# Sheet3.net
KiCad netlist of a schematic drawn in Altium Designer
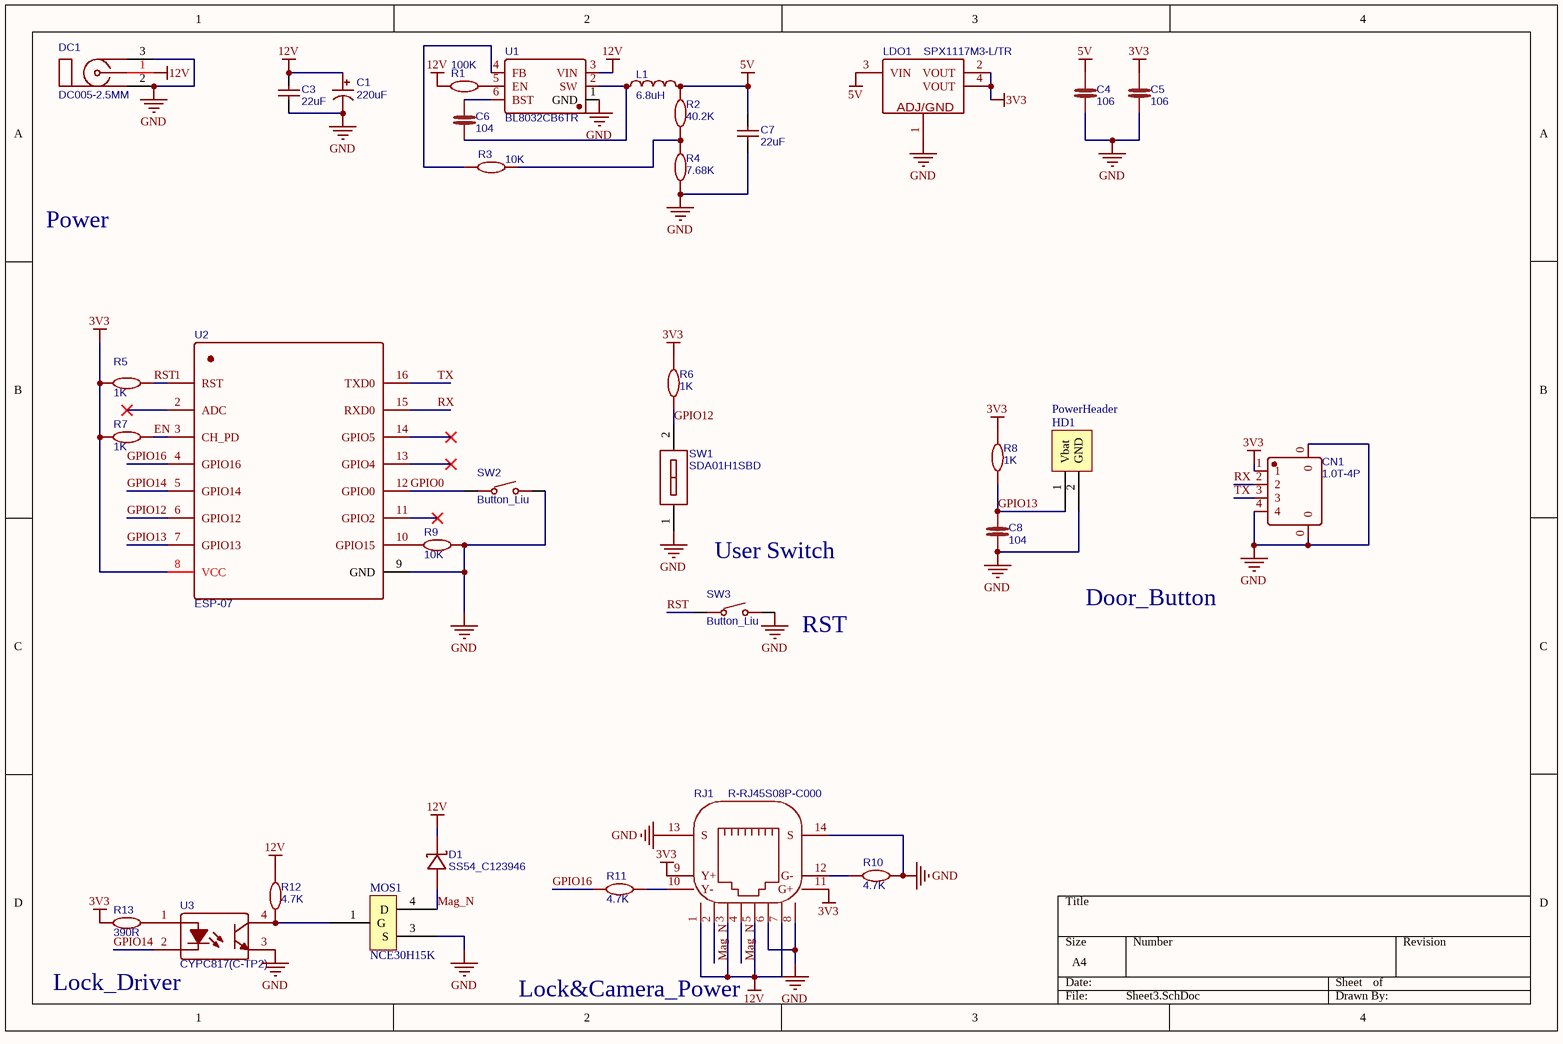
[diagram p0: Sheet3.SchDoc]

(export (version "E")
  (design (tool "Eeschema 10.0.6"))
  (components
    (comp (ref "C1")
      (value "220uF")
      (footprint "CAP-SMD_BD10.0-L10.3-W10.3-FD")
      (fields
        (field (name "BOM_MANUFACTURER PART") "RVT1H221M1010")
        (field (name "BOM_SUPPLIER PART") "C3358")
      )
      (libsource (lib "Power_saving") (part "220uF"))
    )
    (comp (ref "C3")
      (value "22uF")
      (footprint "0805")
      (fields
        (field (name "BOM_MANUFACTURER PART") "TMK212BJ105KG-T")
        (field (name "BOM_SUPPLIER PART") "C92829")
      )
      (libsource (lib "2019_Nudec") (part "1uF"))
    )
    (comp (ref "C4")
      (value "106")
      (footprint "0805")
      (fields (field (name "BOM_MANUFACTURER PART") "?") (field (name "CONTRIBUTOR") "SparkFun"))
      (libsource (lib "抄封装") (part "0.1UF-16V(+-10%)(0402)"))
    )
    (comp (ref "C5")
      (value "106")
      (footprint "0805")
      (fields (field (name "BOM_MANUFACTURER PART") "?") (field (name "CONTRIBUTOR") "SparkFun"))
      (libsource (lib "抄封装") (part "0.1UF-16V(+-10%)(0402)"))
    )
    (comp (ref "C6")
      (value "104")
      (footprint "0402")
      (fields (field (name "BOM_MANUFACTURER PART") "?") (field (name "CONTRIBUTOR") "SparkFun"))
      (libsource (lib "抄封装") (part "0.1UF-16V(+-10%)(0402)"))
    )
    (comp (ref "C7")
      (value "22uF")
      (footprint "0805")
      (fields
        (field (name "BOM_MANUFACTURER PART") "TMK212BJ105KG-T")
        (field (name "BOM_SUPPLIER PART") "C92829")
      )
      (libsource (lib "2019_Nudec") (part "1uF"))
    )
    (comp (ref "C8")
      (value "104")
      (footprint "0402")
      (fields (field (name "BOM_MANUFACTURER PART") "?") (field (name "CONTRIBUTOR") "SparkFun"))
      (libsource (lib "抄封装") (part "0.1UF-16V(+-10%)(0402)"))
    )
    (comp (ref "CN1")
      (value "1.0T-4P")
      (footprint "1.0T-4P-LT")
      (fields (field (name "BOM_SUPPLIER PART") "C145961") (field (name "CONTRIBUTOR") "LCSC"))
      (libsource (lib "Power_saving") (part "1.0T-4P"))
    )
    (comp (ref "D1")
      (value "SS54_C123946")
      (footprint "SMA_L4.4-W2.8-LS5.4-RD")
      (fields
        (field (name "BOM_SUPPLIER PART") "C123946")
        (field (name "BOM_MANUFACTURER PART") "SS54")
        (field (name "CONTRIBUTOR") "LCSC")
      )
      (libsource (lib "Arduino_4G_Weather_Station") (part "SS54_C123946"))
    )
    (comp (ref "DC1")
      (value "DC005-2.5MM")
      (footprint "DC-5020")
      (fields (field (name "BOM_SUPPLIER PART") "C111573"))
      (libsource (lib "Dr.Deng") (part "DC005-2.5MM"))
    )
    (comp (ref "HD1")
      (value "PowerHeader")
      (footprint "PowerHeader")
      (libsource (lib "eg2104") (part "PowerHeader"))
    )
    (comp (ref "L1")
      (value "6.8uH")
      (footprint "L-SMD-6.0X6.0X4.7")
      (fields
        (field (name "BOM_SUPPLIER PART") "C354631")
        (field (name "BOM_MANUFACTURER PART") "CKCS6045-6.8uH/M")
        (field (name "CONTRIBUTOR") "LCSC")
      )
      (libsource (lib "2019_Nudec") (part "6.8uH"))
    )
    (comp (ref "LDO1")
      (value "SPX1117M3-L/TR")
      (footprint "SOT-223")
      (fields (field (name "BOM_SUPPLIER PART") "C67402"))
      (libsource (lib "Arduino_4G_Weather_Station") (part "SPX1117M3-L/TR"))
    )
    (comp (ref "MOS1")
      (value "NCE30H15K")
      (footprint "DPAK228P970X238-3N")
      (libsource (lib "eg2104") (part "IRLR7843"))
    )
    (comp (ref "R1")
      (value "100K")
      (footprint "0402")
      (fields
        (field (name "BOM_SUPPLIER PART") "C340521")
        (field (name "BOM_MANUFACTURER PART") "RMC1/16S-102JTH-M")
        (field (name "CONTRIBUTOR") "LCSC")
      )
      (libsource (lib "抄封装") (part "1K"))
    )
    (comp (ref "R2")
      (value "40.2K")
      (footprint "0402")
      (fields
        (field (name "BOM_SUPPLIER PART") "C340521")
        (field (name "BOM_MANUFACTURER PART") "RMC1/16S-102JTH-M")
        (field (name "CONTRIBUTOR") "LCSC")
      )
      (libsource (lib "抄封装") (part "1K"))
    )
    (comp (ref "R3")
      (value "10K")
      (footprint "0402")
      (fields
        (field (name "BOM_SUPPLIER PART") "C340521")
        (field (name "BOM_MANUFACTURER PART") "RMC1/16S-102JTH-M")
        (field (name "CONTRIBUTOR") "LCSC")
      )
      (libsource (lib "抄封装") (part "1K"))
    )
    (comp (ref "R4")
      (value "7.68K")
      (footprint "0402")
      (fields
        (field (name "BOM_SUPPLIER PART") "C340521")
        (field (name "BOM_MANUFACTURER PART") "RMC1/16S-102JTH-M")
        (field (name "CONTRIBUTOR") "LCSC")
      )
      (libsource (lib "抄封装") (part "1K"))
    )
    (comp (ref "R5")
      (value "1K")
      (footprint "0402")
      (fields
        (field (name "BOM_SUPPLIER PART") "C340521")
        (field (name "BOM_MANUFACTURER PART") "RMC1/16S-102JTH-M")
        (field (name "CONTRIBUTOR") "LCSC")
      )
      (libsource (lib "抄封装") (part "1K"))
    )
    (comp (ref "R6")
      (value "1K")
      (footprint "0402")
      (fields
        (field (name "BOM_SUPPLIER PART") "C340521")
        (field (name "BOM_MANUFACTURER PART") "RMC1/16S-102JTH-M")
        (field (name "CONTRIBUTOR") "LCSC")
      )
      (libsource (lib "抄封装") (part "1K"))
    )
    (comp (ref "R7")
      (value "1K")
      (footprint "0402")
      (fields
        (field (name "BOM_SUPPLIER PART") "C340521")
        (field (name "BOM_MANUFACTURER PART") "RMC1/16S-102JTH-M")
        (field (name "CONTRIBUTOR") "LCSC")
      )
      (libsource (lib "抄封装") (part "1K"))
    )
    (comp (ref "R8")
      (value "1K")
      (footprint "0402")
      (fields
        (field (name "BOM_SUPPLIER PART") "C340521")
        (field (name "BOM_MANUFACTURER PART") "RMC1/16S-102JTH-M")
        (field (name "CONTRIBUTOR") "LCSC")
      )
      (libsource (lib "抄封装") (part "1K"))
    )
    (comp (ref "R9")
      (value "10K")
      (footprint "0402")
      (fields
        (field (name "BOM_SUPPLIER PART") "C340521")
        (field (name "BOM_MANUFACTURER PART") "RMC1/16S-102JTH-M")
        (field (name "CONTRIBUTOR") "LCSC")
      )
      (libsource (lib "抄封装") (part "1K"))
    )
    (comp (ref "R10")
      (value "4.7K")
      (footprint "0402")
      (fields
        (field (name "BOM_SUPPLIER PART") "C340521")
        (field (name "BOM_MANUFACTURER PART") "RMC1/16S-102JTH-M")
        (field (name "CONTRIBUTOR") "LCSC")
      )
      (libsource (lib "抄封装") (part "1K"))
    )
    (comp (ref "R11")
      (value "4.7K")
      (footprint "0402")
      (fields
        (field (name "BOM_SUPPLIER PART") "C340521")
        (field (name "BOM_MANUFACTURER PART") "RMC1/16S-102JTH-M")
        (field (name "CONTRIBUTOR") "LCSC")
      )
      (libsource (lib "抄封装") (part "1K"))
    )
    (comp (ref "R12")
      (value "4.7K")
      (footprint "0402")
      (fields
        (field (name "BOM_SUPPLIER PART") "C340521")
        (field (name "BOM_MANUFACTURER PART") "RMC1/16S-102JTH-M")
        (field (name "CONTRIBUTOR") "LCSC")
      )
      (libsource (lib "抄封装") (part "1K"))
    )
    (comp (ref "R13")
      (value "390R")
      (footprint "0402")
      (fields
        (field (name "BOM_SUPPLIER PART") "C340521")
        (field (name "BOM_MANUFACTURER PART") "RMC1/16S-102JTH-M")
        (field (name "CONTRIBUTOR") "LCSC")
      )
      (libsource (lib "抄封装") (part "1K"))
    )
    (comp (ref "RJ1")
      (value "R-RJ45S08P-C000")
      (footprint "RJ45-TH_12PIN_R-RJ45S08P-C000_PITCH2.54-TL")
      (fields (field (name "BOM_SUPPLIER PART") "C386764") (field (name "CONTRIBUTOR") "LCSC"))
      (libsource (lib "Arduino_4G_Weather_Station") (part "R-RJ45S08P-C000"))
    )
    (comp (ref "SW1")
      (value "SDA01H1SBD")
      (footprint "SDA01H1SBD")
      (fields (field (name "BOM_SUPPLIER PART") "C221944") (field (name "CONTRIBUTOR") "LCSC"))
      (libsource (lib "Arduino_4G_Weather_Station") (part "SDA01H1SBD"))
    )
    (comp (ref "SW2")
      (value "Button_Liu")
      (footprint "SW-SMD_L6.0-W3.5-LS8.0")
      (fields
        (field (name "BOM_SUPPLIER PART") "C318937")
        (field (name "BOM_MANUFACTURER PART") "TS-1101S-C-B-B-W-X")
        (field (name "CONTRIBUTOR") "LCSC")
      )
      (libsource (lib "Arduino_4G_Weather_Station") (part "Button_Liu"))
    )
    (comp (ref "SW3")
      (value "Button_Liu")
      (footprint "SW-SMD_L6.0-W3.5-LS8.0")
      (fields
        (field (name "BOM_SUPPLIER PART") "C318937")
        (field (name "BOM_MANUFACTURER PART") "TS-1101S-C-B-B-W-X")
        (field (name "CONTRIBUTOR") "LCSC")
      )
      (libsource (lib "Arduino_4G_Weather_Station") (part "Button_Liu"))
    )
    (comp (ref "U1")
      (value "BL8032CB6TR")
      (footprint "SOT-23-6")
      (fields (field (name "BOM_SUPPLIER PART") "C93180") (field (name "CONTRIBUTOR") "LCSC"))
      (libsource (lib "2019_Nudec") (part "BL8032CB6TR"))
    )
    (comp (ref "U2")
      (value "ESP-07")
      (footprint "ESP-07")
      (fields (field (name "BOM_SUPPLIER PART") "C82894"))
      (libsource (lib "Dr.Deng") (part "ESP-07"))
    )
    (comp (ref "U3")
      (value "CYPC817(C-TP2)")
      (footprint "SOP-4_4PIN-L4.83-W10.20-PITCH2.54-BL")
      (fields (field (name "BOM_SUPPLIER PART") "C385058") (field (name "CONTRIBUTOR") "LCSC"))
      (libsource (lib "2019_Nudec") (part "CYPC817(C-TP2)"))
    )
  )
  (nets
    (net (code "1") (name "/EN") (class "Default")
      (node (ref "R7") (pin "2") (pinfunction "2_2") (pintype "passive"))
      (node (ref "U2") (pin "3") (pinfunction "CH_PD_3") (pintype "passive"))
    )
    (net (code "2") (name "/GPIO0") (class "Default")
      (node (ref "SW2") (pin "1") (pinfunction "1_1") (pintype "passive"))
      (node (ref "U2") (pin "12") (pinfunction "GPIO0_12") (pintype "passive"))
    )
    (net (code "3") (name "/GPIO12") (class "Default")
      (node (ref "R6") (pin "1") (pinfunction "1_1") (pintype "passive"))
      (node (ref "SW1") (pin "2") (pinfunction "B1_2") (pintype "passive"))
      (node (ref "U2") (pin "6") (pinfunction "GPIO12_6") (pintype "passive"))
    )
    (net (code "4") (name "/GPIO13") (class "Default")
      (node (ref "C8") (pin "1") (pinfunction "1_1") (pintype "passive"))
      (node (ref "HD1") (pin "1") (pinfunction "Vbat_1") (pintype "passive"))
      (node (ref "R8") (pin "1") (pinfunction "1_1") (pintype "passive"))
      (node (ref "U2") (pin "7") (pinfunction "GPIO13_7") (pintype "passive"))
    )
    (net (code "5") (name "/GPIO14") (class "Default")
      (node (ref "U2") (pin "5") (pinfunction "GPIO14_5") (pintype "passive"))
      (node (ref "U3") (pin "2") (pinfunction "CAT_2") (pintype "passive"))
    )
    (net (code "6") (name "/GPIO16") (class "Default")
      (node (ref "R11") (pin "1") (pinfunction "1_1") (pintype "passive"))
      (node (ref "U2") (pin "4") (pinfunction "GPIO16_4") (pintype "passive"))
    )
    (net (code "7") (name "/Mag_N") (class "Default")
      (node (ref "D1") (pin "2") (pinfunction "A_2") (pintype "passive"))
      (node (ref "MOS1") (pin "4") (pinfunction "D_4") (pintype "passive"))
      (node (ref "RJ1") (pin "2") (pinfunction "2_2") (pintype "passive"))
      (node (ref "RJ1") (pin "4") (pinfunction "4_4") (pintype "passive"))
    )
    (net (code "8") (name "/RST") (class "Default")
      (node (ref "R5") (pin "2") (pinfunction "2_2") (pintype "passive"))
      (node (ref "SW3") (pin "1") (pinfunction "1_1") (pintype "passive"))
      (node (ref "U2") (pin "1") (pinfunction "RST_1") (pintype "passive"))
    )
    (net (code "9") (name "/RX") (class "Default")
      (node (ref "CN1") (pin "2") (pinfunction "2_2") (pintype "passive"))
      (node (ref "U2") (pin "15") (pinfunction "RXD0_15") (pintype "passive"))
    )
    (net (code "10") (name "/TX") (class "Default")
      (node (ref "CN1") (pin "3") (pinfunction "3_3") (pintype "passive"))
      (node (ref "U2") (pin "16") (pinfunction "TXD0_16") (pintype "passive"))
    )
    (net (code "11") (name "3V3") (class "Default")
      (node (ref "C5") (pin "1") (pinfunction "1_1") (pintype "passive"))
      (node (ref "CN1") (pin "1") (pinfunction "1_1") (pintype "passive"))
      (node (ref "LDO1") (pin "2") (pinfunction "VOUT_2") (pintype "passive"))
      (node (ref "LDO1") (pin "4") (pinfunction "VOUT_4") (pintype "passive"))
      (node (ref "R13") (pin "2") (pinfunction "2_2") (pintype "passive"))
      (node (ref "R5") (pin "1") (pinfunction "1_1") (pintype "passive"))
      (node (ref "R6") (pin "2") (pinfunction "2_2") (pintype "passive"))
      (node (ref "R7") (pin "1") (pinfunction "1_1") (pintype "passive"))
      (node (ref "R8") (pin "2") (pinfunction "2_2") (pintype "passive"))
      (node (ref "RJ1") (pin "11") (pinfunction "G+_11") (pintype "passive"))
      (node (ref "RJ1") (pin "9") (pinfunction "Y+_9") (pintype "passive"))
      (node (ref "U2") (pin "8") (pinfunction "VCC_8") (pintype "passive"))
    )
    (net (code "12") (name "5V") (class "Default")
      (node (ref "C4") (pin "1") (pinfunction "1_1") (pintype "passive"))
      (node (ref "C7") (pin "2") (pinfunction "2_2") (pintype "passive"))
      (node (ref "L1") (pin "2") (pinfunction "2_2") (pintype "passive"))
      (node (ref "LDO1") (pin "3") (pinfunction "VIN_3") (pintype "passive"))
      (node (ref "R2") (pin "1") (pinfunction "1_1") (pintype "passive"))
    )
    (net (code "13") (name "12V") (class "Default")
      (node (ref "C1") (pin "1") (pinfunction "1_1") (pintype "passive"))
      (node (ref "C3") (pin "2") (pinfunction "2_2") (pintype "passive"))
      (node (ref "D1") (pin "1") (pinfunction "K_1") (pintype "passive"))
      (node (ref "DC1") (pin "1") (pinfunction "VCC_1") (pintype "passive"))
      (node (ref "R1") (pin "2") (pinfunction "2_2") (pintype "passive"))
      (node (ref "R12") (pin "1") (pinfunction "1_1") (pintype "passive"))
      (node (ref "RJ1") (pin "1") (pinfunction "1_1") (pintype "passive"))
      (node (ref "RJ1") (pin "3") (pinfunction "3_3") (pintype "passive"))
      (node (ref "RJ1") (pin "5") (pinfunction "5_5") (pintype "passive"))
      (node (ref "RJ1") (pin "7") (pinfunction "7_7") (pintype "passive"))
      (node (ref "U1") (pin "3") (pinfunction "VIN_3") (pintype "passive"))
    )
    (net (code "14") (name "GND") (class "Default")
      (node (ref "C1") (pin "2") (pinfunction "2_2") (pintype "passive"))
      (node (ref "C3") (pin "1") (pinfunction "1_1") (pintype "passive"))
      (node (ref "C4") (pin "2") (pinfunction "2_2") (pintype "passive"))
      (node (ref "C5") (pin "2") (pinfunction "2_2") (pintype "passive"))
      (node (ref "C7") (pin "1") (pinfunction "1_1") (pintype "passive"))
      (node (ref "C8") (pin "2") (pinfunction "2_2") (pintype "passive"))
      (node (ref "CN1") (pin "0") (pinfunction "0_0") (pintype "passive"))
      (node (ref "CN1") (pin "4") (pinfunction "4_4") (pintype "passive"))
      (node (ref "DC1") (pin "2") (pinfunction "2_2") (pintype "passive"))
      (node (ref "DC1") (pin "3") (pinfunction "3_3") (pintype "passive"))
      (node (ref "HD1") (pin "2") (pinfunction "GND_2") (pintype "passive"))
      (node (ref "LDO1") (pin "1") (pinfunction "ADJ_1") (pintype "passive"))
      (node (ref "MOS1") (pin "3") (pinfunction "S_3") (pintype "passive"))
      (node (ref "R10") (pin "2") (pinfunction "2_2") (pintype "passive"))
      (node (ref "R4") (pin "2") (pinfunction "2_2") (pintype "passive"))
      (node (ref "R9") (pin "2") (pinfunction "2_2") (pintype "passive"))
      (node (ref "RJ1") (pin "13") (pinfunction "S_13") (pintype "passive"))
      (node (ref "RJ1") (pin "14") (pinfunction "S_14") (pintype "passive"))
      (node (ref "RJ1") (pin "6") (pinfunction "6_6") (pintype "passive"))
      (node (ref "RJ1") (pin "8") (pinfunction "8_8") (pintype "passive"))
      (node (ref "SW1") (pin "1") (pinfunction "A1_1") (pintype "passive"))
      (node (ref "SW2") (pin "2") (pinfunction "2_2") (pintype "passive"))
      (node (ref "SW3") (pin "2") (pinfunction "2_2") (pintype "passive"))
      (node (ref "U1") (pin "1") (pinfunction "GND_1") (pintype "passive"))
      (node (ref "U2") (pin "9") (pinfunction "GND_9") (pintype "passive"))
      (node (ref "U3") (pin "3") (pinfunction "EMI_3") (pintype "passive"))
    )
    (net (code "15") (name "Net-(MOS1-G)") (class "Default")
      (node (ref "MOS1") (pin "1") (pinfunction "G_1") (pintype "passive"))
      (node (ref "R12") (pin "2") (pinfunction "2_2") (pintype "passive"))
      (node (ref "U3") (pin "4") (pinfunction "COL_4") (pintype "passive"))
    )
    (net (code "16") (name "Net-(R2-Pad2)") (class "Default")
      (node (ref "R2") (pin "2") (pinfunction "2_2") (pintype "passive"))
      (node (ref "R3") (pin "1") (pinfunction "1_1") (pintype "passive"))
      (node (ref "R4") (pin "1") (pinfunction "1_1") (pintype "passive"))
    )
    (net (code "17") (name "Net-(RJ1-G-)") (class "Default")
      (node (ref "R10") (pin "1") (pinfunction "1_1") (pintype "passive"))
      (node (ref "RJ1") (pin "12") (pinfunction "G-_12") (pintype "passive"))
    )
    (net (code "18") (name "Net-(RJ1-Y-)") (class "Default")
      (node (ref "R11") (pin "2") (pinfunction "2_2") (pintype "passive"))
      (node (ref "RJ1") (pin "10") (pinfunction "Y-_10") (pintype "passive"))
    )
    (net (code "19") (name "Net-(U1-BST)") (class "Default")
      (node (ref "C6") (pin "2") (pinfunction "2_2") (pintype "passive"))
      (node (ref "U1") (pin "6") (pinfunction "BST_6") (pintype "passive"))
    )
    (net (code "20") (name "Net-(U1-EN)") (class "Default")
      (node (ref "R1") (pin "1") (pinfunction "1_1") (pintype "passive"))
      (node (ref "U1") (pin "5") (pinfunction "EN_5") (pintype "passive"))
    )
    (net (code "21") (name "Net-(U1-FB)") (class "Default")
      (node (ref "R3") (pin "2") (pinfunction "2_2") (pintype "passive"))
      (node (ref "U1") (pin "4") (pinfunction "FB_4") (pintype "passive"))
    )
    (net (code "22") (name "Net-(U1-SW)") (class "Default")
      (node (ref "C6") (pin "1") (pinfunction "1_1") (pintype "passive"))
      (node (ref "L1") (pin "1") (pinfunction "1_1") (pintype "passive"))
      (node (ref "U1") (pin "2") (pinfunction "SW_2") (pintype "passive"))
    )
    (net (code "23") (name "Net-(U2-GPIO15)") (class "Default")
      (node (ref "R9") (pin "1") (pinfunction "1_1") (pintype "passive"))
      (node (ref "U2") (pin "10") (pinfunction "GPIO15_10") (pintype "passive"))
    )
    (net (code "24") (name "Net-(U3-AN)") (class "Default")
      (node (ref "R13") (pin "1") (pinfunction "1_1") (pintype "passive"))
      (node (ref "U3") (pin "1") (pinfunction "AN_1") (pintype "passive"))
    )
    (net (code "25") (name "unconnected-(U2-ADC-Pad2)") (class "Default")
      (node (ref "U2") (pin "2") (pinfunction "ADC_2") (pintype "passive+no_connect"))
    )
    (net (code "26") (name "unconnected-(U2-GPIO2-Pad11)") (class "Default")
      (node (ref "U2") (pin "11") (pinfunction "GPIO2_11") (pintype "passive+no_connect"))
    )
    (net (code "27") (name "unconnected-(U2-GPIO4-Pad13)") (class "Default")
      (node (ref "U2") (pin "13") (pinfunction "GPIO4_13") (pintype "passive+no_connect"))
    )
    (net (code "28") (name "unconnected-(U2-GPIO5-Pad14)") (class "Default")
      (node (ref "U2") (pin "14") (pinfunction "GPIO5_14") (pintype "passive+no_connect"))
    )
  )
)
